# Sample_v1.net
KiCad netlist of a schematic drawn in Altium Designer
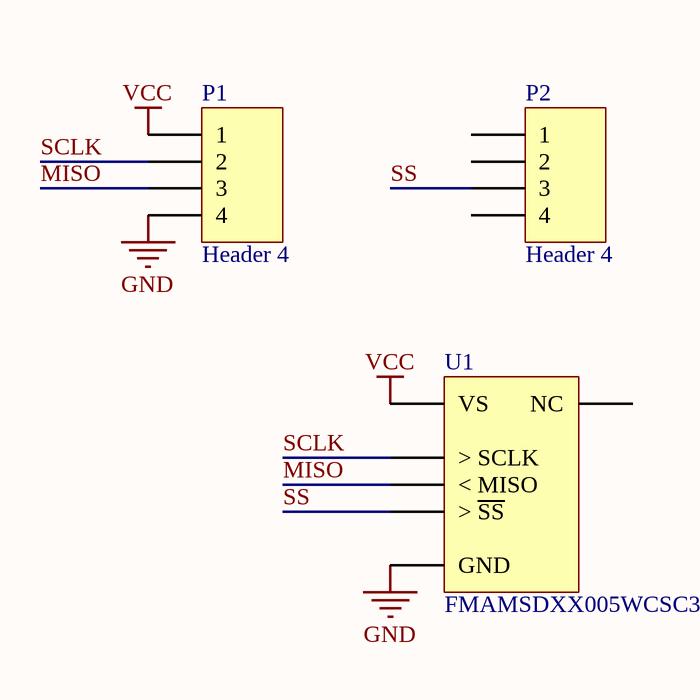
[diagram p0: Sample_v1.SchDoc]

(export (version "E")
  (design (tool "Eeschema 10.0.6"))
  (components
    (comp (ref "P1")
      (value "Header 4")
      (footprint "HDR1X4")
      (description "Header, 4-Pin")
      (fields (field (name "PUBLISHER") "Altium Limited"))
      (libsource (lib "FMA_Sensor") (part "Header 4"))
    )
    (comp (ref "P2")
      (value "Header 4")
      (footprint "HDR1X4")
      (description "Header, 4-Pin")
      (fields (field (name "PUBLISHER") "Altium Limited"))
      (libsource (lib "FMA_Sensor") (part "Header 4"))
    )
    (comp (ref "U1")
      (value "FMAMSDXX005WCSC3")
      (footprint "FMA_MICROFORCE_6")
      (libsource (lib "FMA_Sensor") (part "FMAMSDXX005WCSC3"))
    )
  )
  (nets
    (net (code "1") (name "/MISO") (class "Default")
      (node (ref "P1") (pin "3") (pinfunction "3_3") (pintype "passive"))
      (node (ref "U1") (pin "5") (pinfunction "<_MISO_5") (pintype "passive"))
    )
    (net (code "2") (name "/SCLK") (class "Default")
      (node (ref "P1") (pin "2") (pinfunction "2_2") (pintype "passive"))
      (node (ref "U1") (pin "4") (pinfunction ">_SCLK_4") (pintype "passive"))
    )
    (net (code "3") (name "/SS") (class "Default")
      (node (ref "P2") (pin "3") (pinfunction "3_3") (pintype "passive"))
      (node (ref "U1") (pin "2") (pinfunction ">_~{SS}_2") (pintype "passive"))
    )
    (net (code "4") (name "GND") (class "Default")
      (node (ref "P1") (pin "4") (pinfunction "4_4") (pintype "passive"))
      (node (ref "U1") (pin "3") (pinfunction "GND_3") (pintype "passive"))
    )
    (net (code "5") (name "VCC") (class "Default")
      (node (ref "P1") (pin "1") (pinfunction "1_1") (pintype "passive"))
      (node (ref "U1") (pin "1") (pinfunction "VS_1") (pintype "passive"))
    )
    (net (code "6") (name "unconnected-(P2-Pad1)") (class "Default")
      (node (ref "P2") (pin "1") (pinfunction "1_1") (pintype "passive"))
    )
    (net (code "7") (name "unconnected-(P2-Pad2)") (class "Default")
      (node (ref "P2") (pin "2") (pinfunction "2_2") (pintype "passive"))
    )
    (net (code "8") (name "unconnected-(P2-Pad4)") (class "Default")
      (node (ref "P2") (pin "4") (pinfunction "4_4") (pintype "passive"))
    )
    (net (code "9") (name "unconnected-(U1-NC-Pad6)") (class "Default")
      (node (ref "U1") (pin "6") (pinfunction "NC_6") (pintype "passive"))
    )
  )
)
